# tiny2313.net
KiCad netlist of a schematic drawn in EAGLE
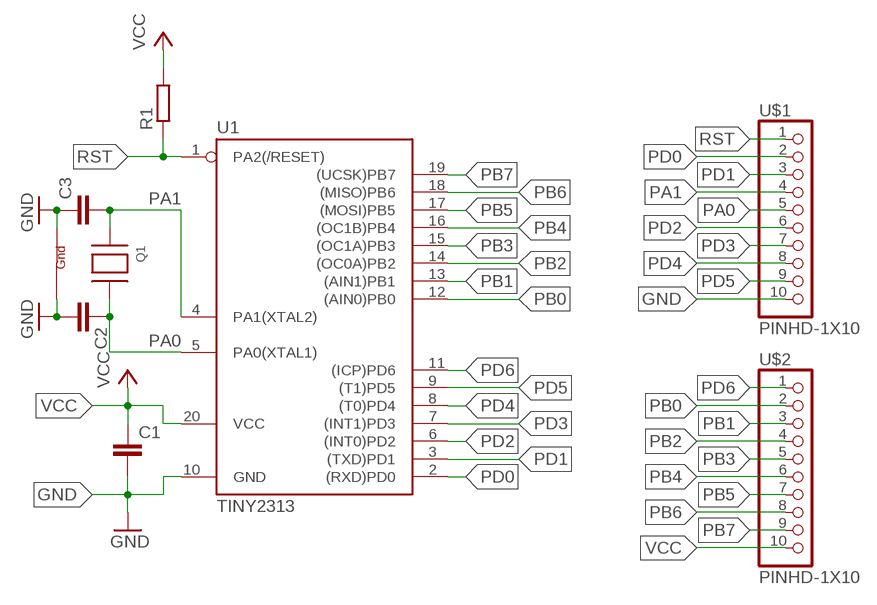
[diagram p0: schematic, sheet 1]

(export (version "E")
  (design (tool "Eeschema 10.0.6"))
  (components
    (comp (ref "C1")
      (value "C-EUC0805")
      (footprint "eagle-import:C0805")
      (libsource (lib "eagle-import") (part "C-EUC0805"))
    )
    (comp (ref "C2")
      (value "C-EUC0805")
      (footprint "eagle-import:C0805")
      (libsource (lib "eagle-import") (part "C-EUC0805"))
    )
    (comp (ref "C3")
      (value "C-EUC0805")
      (footprint "eagle-import:C0805")
      (libsource (lib "eagle-import") (part "C-EUC0805"))
    )
    (comp (ref "Q1")
      (value "XTAL-4-3225")
      (footprint "eagle-import:NX3225")
      (libsource (lib "eagle-import") (part "XTAL-4-3225"))
    )
    (comp (ref "R1")
      (value "R-EU_R0805")
      (footprint "eagle-import:R0805")
      (libsource (lib "eagle-import") (part "R-EU_R0805"))
    )
    (comp (ref "U$1")
      (value "PINHD-1X10")
      (footprint "eagle-import:1X10-BIG")
      (libsource (lib "eagle-import") (part "PINHD-1X10"))
    )
    (comp (ref "U$2")
      (value "PINHD-1X10")
      (footprint "eagle-import:1X10-BIG")
      (libsource (lib "eagle-import") (part "PINHD-1X10"))
    )
    (comp (ref "U1")
      (value "TINY2313")
      (footprint "eagle-import:SO20L$")
      (libsource (lib "eagle-import") (part "TINY2313-S"))
    )
  )
  (nets
    (net (code "1") (name "GND") (class "Default")
      (node (ref "C1") (pin "2") (pinfunction "2_2") (pintype "passive"))
      (node (ref "C2") (pin "2") (pinfunction "2_2") (pintype "passive"))
      (node (ref "C3") (pin "1") (pinfunction "1_1") (pintype "passive"))
      (node (ref "Q1") (pin "2") (pinfunction "G2_2") (pintype "power_in"))
      (node (ref "Q1") (pin "4") (pinfunction "G1_4") (pintype "power_in"))
      (node (ref "U$1") (pin "10") (pinfunction "10_10") (pintype "passive"))
      (node (ref "U1") (pin "10") (pinfunction "GND_10") (pintype "power_in"))
    )
    (net (code "2") (name "PA0") (class "Default")
      (node (ref "C2") (pin "1") (pinfunction "1_1") (pintype "passive"))
      (node (ref "Q1") (pin "3") (pinfunction "X2_3") (pintype "bidirectional"))
      (node (ref "U$1") (pin "5") (pinfunction "5_5") (pintype "passive"))
      (node (ref "U1") (pin "5") (pinfunction "PA0(XTAL1)_5") (pintype "bidirectional"))
    )
    (net (code "3") (name "PA1") (class "Default")
      (node (ref "C3") (pin "2") (pinfunction "2_2") (pintype "passive"))
      (node (ref "Q1") (pin "1") (pinfunction "X1_1") (pintype "bidirectional"))
      (node (ref "U$1") (pin "4") (pinfunction "4_4") (pintype "passive"))
      (node (ref "U1") (pin "4") (pinfunction "PA1(XTAL2)_4") (pintype "bidirectional"))
    )
    (net (code "4") (name "PB0") (class "Default")
      (node (ref "U$2") (pin "2") (pinfunction "2_2") (pintype "passive"))
      (node (ref "U1") (pin "12") (pinfunction "(AIN0)PB0_12") (pintype "bidirectional"))
    )
    (net (code "5") (name "PB1") (class "Default")
      (node (ref "U$2") (pin "3") (pinfunction "3_3") (pintype "passive"))
      (node (ref "U1") (pin "13") (pinfunction "(AIN1)PB1_13") (pintype "bidirectional"))
    )
    (net (code "6") (name "PB2") (class "Default")
      (node (ref "U$2") (pin "4") (pinfunction "4_4") (pintype "passive"))
      (node (ref "U1") (pin "14") (pinfunction "(OC0A)PB2_14") (pintype "bidirectional"))
    )
    (net (code "7") (name "PB3") (class "Default")
      (node (ref "U$2") (pin "5") (pinfunction "5_5") (pintype "passive"))
      (node (ref "U1") (pin "15") (pinfunction "(OC1A)PB3_15") (pintype "bidirectional"))
    )
    (net (code "8") (name "PB4") (class "Default")
      (node (ref "U$2") (pin "6") (pinfunction "6_6") (pintype "passive"))
      (node (ref "U1") (pin "16") (pinfunction "(OC1B)PB4_16") (pintype "bidirectional"))
    )
    (net (code "9") (name "PB5") (class "Default")
      (node (ref "U$2") (pin "7") (pinfunction "7_7") (pintype "passive"))
      (node (ref "U1") (pin "17") (pinfunction "(MOSI)PB5_17") (pintype "bidirectional"))
    )
    (net (code "10") (name "PB6") (class "Default")
      (node (ref "U$2") (pin "8") (pinfunction "8_8") (pintype "passive"))
      (node (ref "U1") (pin "18") (pinfunction "(MISO)PB6_18") (pintype "bidirectional"))
    )
    (net (code "11") (name "PB7") (class "Default")
      (node (ref "U$2") (pin "9") (pinfunction "9_9") (pintype "passive"))
      (node (ref "U1") (pin "19") (pinfunction "(UCSK)PB7_19") (pintype "bidirectional"))
    )
    (net (code "12") (name "PD0") (class "Default")
      (node (ref "U$1") (pin "2") (pinfunction "2_2") (pintype "passive"))
      (node (ref "U1") (pin "2") (pinfunction "(RXD)PD0_2") (pintype "bidirectional"))
    )
    (net (code "13") (name "PD1") (class "Default")
      (node (ref "U$1") (pin "3") (pinfunction "3_3") (pintype "passive"))
      (node (ref "U1") (pin "3") (pinfunction "(TXD)PD1_3") (pintype "bidirectional"))
    )
    (net (code "14") (name "PD2") (class "Default")
      (node (ref "U$1") (pin "6") (pinfunction "6_6") (pintype "passive"))
      (node (ref "U1") (pin "6") (pinfunction "(INT0)PD2_6") (pintype "bidirectional"))
    )
    (net (code "15") (name "PD3") (class "Default")
      (node (ref "U$1") (pin "7") (pinfunction "7_7") (pintype "passive"))
      (node (ref "U1") (pin "7") (pinfunction "(INT1)PD3_7") (pintype "bidirectional"))
    )
    (net (code "16") (name "PD4") (class "Default")
      (node (ref "U$1") (pin "8") (pinfunction "8_8") (pintype "passive"))
      (node (ref "U1") (pin "8") (pinfunction "(T0)PD4_8") (pintype "bidirectional"))
    )
    (net (code "17") (name "PD5") (class "Default")
      (node (ref "U$1") (pin "9") (pinfunction "9_9") (pintype "passive"))
      (node (ref "U1") (pin "9") (pinfunction "(T1)PD5_9") (pintype "bidirectional"))
    )
    (net (code "18") (name "PD6") (class "Default")
      (node (ref "U$2") (pin "1") (pinfunction "1_1") (pintype "passive"))
      (node (ref "U1") (pin "11") (pinfunction "(ICP)PD6_11") (pintype "bidirectional"))
    )
    (net (code "19") (name "RST") (class "Default")
      (node (ref "R1") (pin "1") (pinfunction "1_1") (pintype "passive"))
      (node (ref "U$1") (pin "1") (pinfunction "1_1") (pintype "passive"))
      (node (ref "U1") (pin "1") (pinfunction "PA2(/RESET)_1") (pintype "input"))
    )
    (net (code "20") (name "VCC") (class "Default")
      (node (ref "C1") (pin "1") (pinfunction "1_1") (pintype "passive"))
      (node (ref "R1") (pin "2") (pinfunction "2_2") (pintype "passive"))
      (node (ref "U$2") (pin "10") (pinfunction "10_10") (pintype "passive"))
      (node (ref "U1") (pin "20") (pinfunction "VCC_20") (pintype "power_in"))
    )
  )
)
